# STM32_Power.net
KiCad netlist of a schematic drawn in Altium Designer
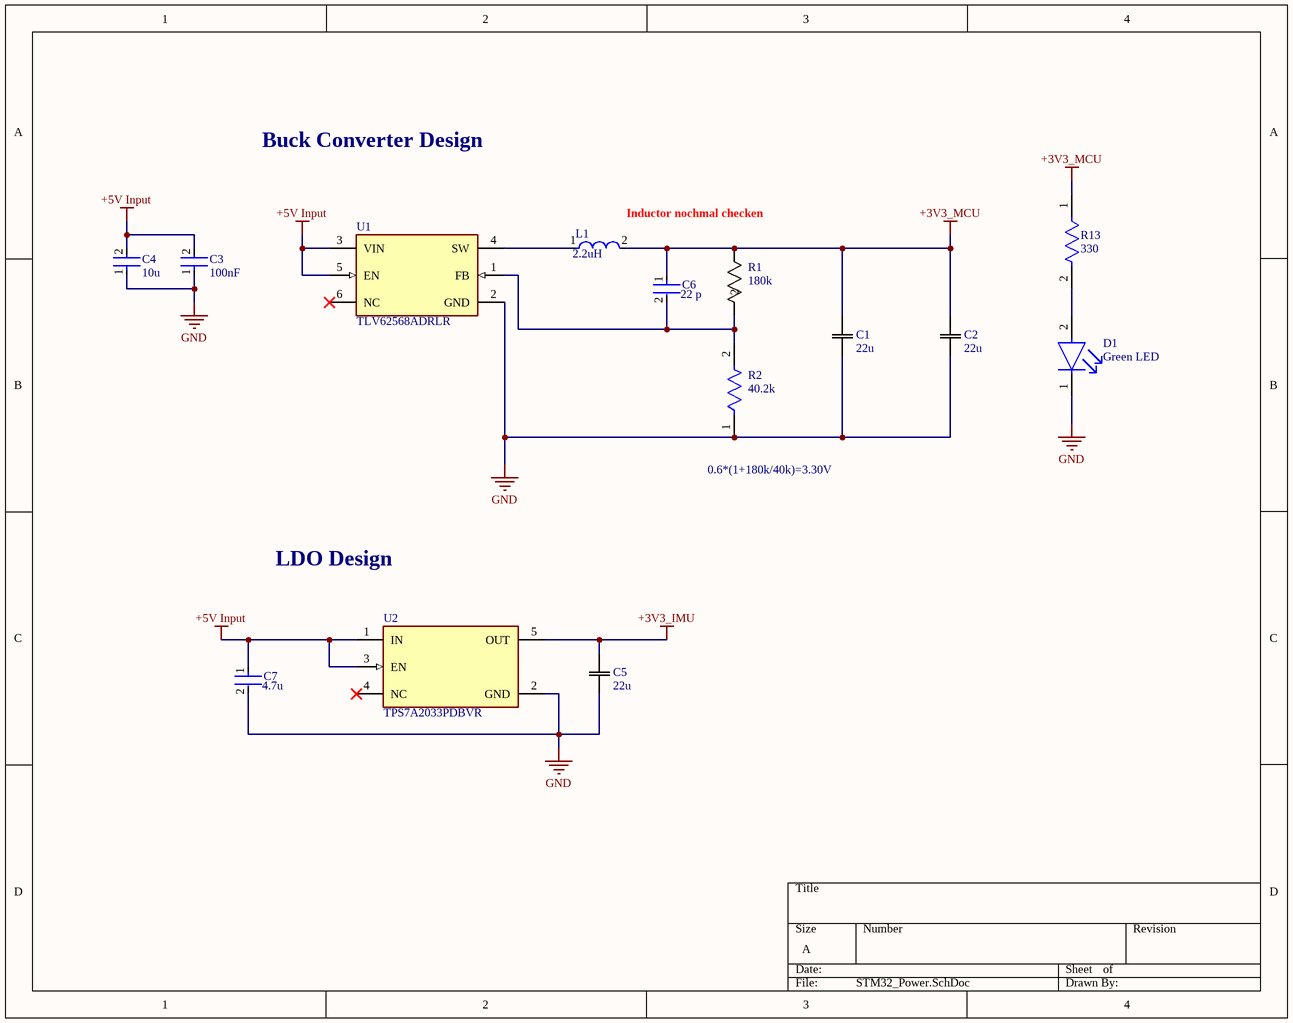
[diagram p0: STM32_Power.SchDoc]

(export (version "E")
  (design (tool "Eeschema 10.0.6"))
  (components
    (comp (ref "C1")
      (value "22u")
      (footprint "CAP_MSAS16-8_TAY")
      (description "MSASL168BB5226MTNA01, CAP CER 22UF 10V X5R 0603")
      (fields
        (field (name "MANUFACTURER_PART_NUMBER") "MSASL168BB5226MTNA01")
        (field (name "COPYRIGHT") "Copyright (C) 2026 Ultra Librarian. All rights reserved.")
      )
      (libsource (lib "Schlib1") (part "MSASL168BB5226MTNA01"))
    )
    (comp (ref "C2")
      (value "22u")
      (footprint "CAP_MSAS16-8_TAY")
      (description "MSASL168BB5226MTNA01, CAP CER 22UF 10V X5R 0603")
      (fields
        (field (name "MANUFACTURER_PART_NUMBER") "MSASL168BB5226MTNA01")
        (field (name "COPYRIGHT") "Copyright (C) 2026 Ultra Librarian. All rights reserved.")
      )
      (libsource (lib "Schlib1") (part "MSASL168BB5226MTNA01"))
    )
    (comp (ref "C3")
      (value "0603B104K250CT")
      (footprint "FP-0603B104K250CT-IPC_C")
      (description "CAP CER 0.1UF 25V X7R 0603")
      (fields (field (name "TOLERANCE") "10%") (field (name "CAPACITANCE") "100nF"))
      (libsource (lib "Altium Content Vault") (part "b4654b650e69147ec39a6b967a45e02"))
    )
    (comp (ref "C4")
      (value "10u")
      (footprint "FP-GRM188-0_2-IPC_B")
      (description "Chip Multilayer Ceramic Capacitors for General Purpose, 0603, 10uF, X7R, 15%, 20%, 10V")
      (fields (field (name "Comment") "GRM188Z71A106MA73D"))
      (libsource (lib "Altium Content Vault") (part "11868f565c42a9108669ba33697ecf6"))
    )
    (comp (ref "C5")
      (value "22u")
      (footprint "CAP_MSAS16-8_TAY")
      (description "MSASL168BB5226MTNA01, CAP CER 22UF 10V X5R 0603")
      (fields
        (field (name "MANUFACTURER_PART_NUMBER") "MSASL168BB5226MTNA01")
        (field (name "COPYRIGHT") "Copyright (C) 2026 Ultra Librarian. All rights reserved.")
      )
      (libsource (lib "Schlib1") (part "MSASL168BB5226MTNA01"))
    )
    (comp (ref "C6")
      (value "22 p")
      (footprint "FP-C0603C-CF-MFG")
      (description "C0603 22 pF C0G 30ppm/°C 1.00% 50 V")
      (fields
        (field (name "TOLERANCE") "0.01")
        (field (name "MANUFACTURER PART NUMBER") "C0603C220F5GACAUTO")
      )
      (libsource (lib "Altium Content Vault") (part "b4654b650e69147ec39a6b967a45e02"))
    )
    (comp (ref "C7")
      (value "GRM188R61C475KE11J")
      (footprint "FP-GRM188-0_15-MFG")
      (description "Chip Multilayer Ceramic Capacitors for General Purpose, 0603, 4.7uF, X5R, 15%, 10%, 16V")
      (fields (field (name "TOLERANCE") "10%") (field (name "CAPACITANCE") "4.7u"))
      (libsource (lib "Altium Content Vault") (part "02cd4be3c70576c341d710602a673aa"))
    )
    (comp (ref "D1")
      (value "Green LED")
      (footprint "FP-LTST-C190KGKT-MFG")
      (description "LED GREEN CLEAR CHIP SMDLTST-C190KGKT")
      (libsource (lib "Altium Content Vault") (part "8706943c75ba83719d021d2fdc84c58"))
    )
    (comp (ref "L1")
      (value "2.2uH")
      (footprint "FP-IHLP-1616AB-FP_1_8545x-MFG")
      (description "Fixed Inductors Commercial Low DCR Series SMT 2.2uH 2.75A 83.5mΩ 20%")
      (fields (field (name "TOLERANCE") "20%") (field (name "Comment") "IHLP1616ABER2R2M11"))
      (libsource (lib "Altium Content Vault") (part "725321dda6339637d4d059423bc1c3c"))
    )
    (comp (ref "R1")
      (value "180k")
      (footprint "RC0603N_YAG")
      (description "Description")
      (fields
        (field (name "MANUFACTURER_PART_NUMBER") "RC0603FR-07180KL")
        (field (name "COPYRIGHT") "Copyright (C) 2025 Ultra Librarian. All rights reserved.")
      )
      (libsource (lib "Schlib1") (part "RC0603FR-07180KL"))
    )
    (comp (ref "R2")
      (value "RMCF0603FT40K2")
      (footprint "FP-RMCF0603-IPC_A")
      (description "40.2kΩ ±1% 0.1W 0603 Thick Film Chip Resistor AEC-Q200 compliant")
      (fields (field (name "TOLERANCE") "1%") (field (name "RESISTANCE") "40.2k"))
      (libsource (lib "Altium Content Vault") (part "1029c3af85768c4190bb7ad29bc67b5"))
    )
    (comp (ref "R13")
      (value "RT0603FRD07330RL")
      (footprint "FP-RT0603-MFG")
      (description "RES SMD 330 OHM 1% 1/10W 0603")
      (fields
        (field (name "RESISTANCE") "330")
        (field (name "TOLERANCE") "0.01")
        (field (name "OCTOPART") "https://octopart.com/rt0603frd07330rl-yageo-71395358")
      )
      (libsource (lib "Altium Content Vault") (part "1029c3af85768c4190bb7ad29bc67b5"))
    )
    (comp (ref "U1")
      (value "TLV62568ADRLR")
      (footprint "FP-DRL0006A-MFG")
      (description "IC REG BUCK ADJUSTABLE 2A SOT563")
      (libsource (lib "Altium Content Vault") (part "c065b8f3016c1e0e14a773cb518fcf3"))
    )
    (comp (ref "U2")
      (value "TPS7A2033PDBVR")
      (footprint "FP-DBV0005A-MFG")
      (description "IC REG LINEAR 3.3V 300MA SOT23-5")
      (libsource (lib "Altium Content Vault") (part "76aa7ad0ceb1012e0d85aeafc53095f"))
    )
  )
  (nets
    (net (code "1") (name "+3V3_IMU") (class "Default")
      (node (ref "C5") (pin "2") (pinfunction "2_2") (pintype "passive"))
      (node (ref "U2") (pin "5") (pinfunction "OUT_5") (pintype "passive"))
    )
    (net (code "2") (name "+3V3_MCU") (class "Default")
      (node (ref "C1") (pin "2") (pinfunction "2_2") (pintype "passive"))
      (node (ref "C2") (pin "2") (pinfunction "2_2") (pintype "passive"))
      (node (ref "C6") (pin "1") (pinfunction "1_1") (pintype "passive"))
      (node (ref "L1") (pin "2") (pinfunction "2_2") (pintype "passive"))
      (node (ref "R1") (pin "1") (pinfunction "1_1") (pintype "passive"))
      (node (ref "R13") (pin "1") (pinfunction "1_1") (pintype "passive"))
    )
    (net (code "3") (name "+5V Input") (class "Default")
      (node (ref "C3") (pin "2") (pinfunction "2_2") (pintype "passive"))
      (node (ref "C4") (pin "2") (pinfunction "2_2") (pintype "passive"))
      (node (ref "C7") (pin "1") (pinfunction "1_1") (pintype "passive"))
      (node (ref "U1") (pin "3") (pinfunction "VIN_3") (pintype "power_in"))
      (node (ref "U1") (pin "5") (pinfunction "EN_5") (pintype "input"))
      (node (ref "U2") (pin "1") (pinfunction "IN_1") (pintype "power_in"))
      (node (ref "U2") (pin "3") (pinfunction "EN_3") (pintype "input"))
    )
    (net (code "4") (name "GND") (class "Default")
      (node (ref "C1") (pin "1") (pinfunction "1_1") (pintype "passive"))
      (node (ref "C2") (pin "1") (pinfunction "1_1") (pintype "passive"))
      (node (ref "C3") (pin "1") (pinfunction "1_1") (pintype "passive"))
      (node (ref "C4") (pin "1") (pinfunction "1_1") (pintype "passive"))
      (node (ref "C5") (pin "1") (pinfunction "1_1") (pintype "passive"))
      (node (ref "C7") (pin "2") (pinfunction "2_2") (pintype "passive"))
      (node (ref "D1") (pin "1") (pinfunction "C_1") (pintype "passive"))
      (node (ref "R2") (pin "1") (pinfunction "1_1") (pintype "passive"))
      (node (ref "U1") (pin "2") (pinfunction "GND_2") (pintype "power_in"))
      (node (ref "U2") (pin "2") (pinfunction "GND_2") (pintype "power_in"))
    )
    (net (code "5") (name "Net-(D1-A)") (class "Default")
      (node (ref "D1") (pin "2") (pinfunction "A_2") (pintype "passive"))
      (node (ref "R13") (pin "2") (pinfunction "2_2") (pintype "passive"))
    )
    (net (code "6") (name "Net-(U1-FB)") (class "Default")
      (node (ref "C6") (pin "2") (pinfunction "2_2") (pintype "passive"))
      (node (ref "R1") (pin "2") (pinfunction "2_2") (pintype "passive"))
      (node (ref "R2") (pin "2") (pinfunction "2_2") (pintype "passive"))
      (node (ref "U1") (pin "1") (pinfunction "FB_1") (pintype "input"))
    )
    (net (code "7") (name "Net-(U1-SW)") (class "Default")
      (node (ref "L1") (pin "1") (pinfunction "1_1") (pintype "passive"))
      (node (ref "U1") (pin "4") (pinfunction "SW_4") (pintype "passive"))
    )
    (net (code "8") (name "unconnected-(U1-NC-Pad6)") (class "Default")
      (node (ref "U1") (pin "6") (pinfunction "NC_6") (pintype "passive+no_connect"))
    )
    (net (code "9") (name "unconnected-(U2-NC-Pad4)") (class "Default")
      (node (ref "U2") (pin "4") (pinfunction "NC_4") (pintype "passive+no_connect"))
    )
  )
)
